# Smart_Bottle.net
KiCad netlist of a schematic drawn in Altium Designer
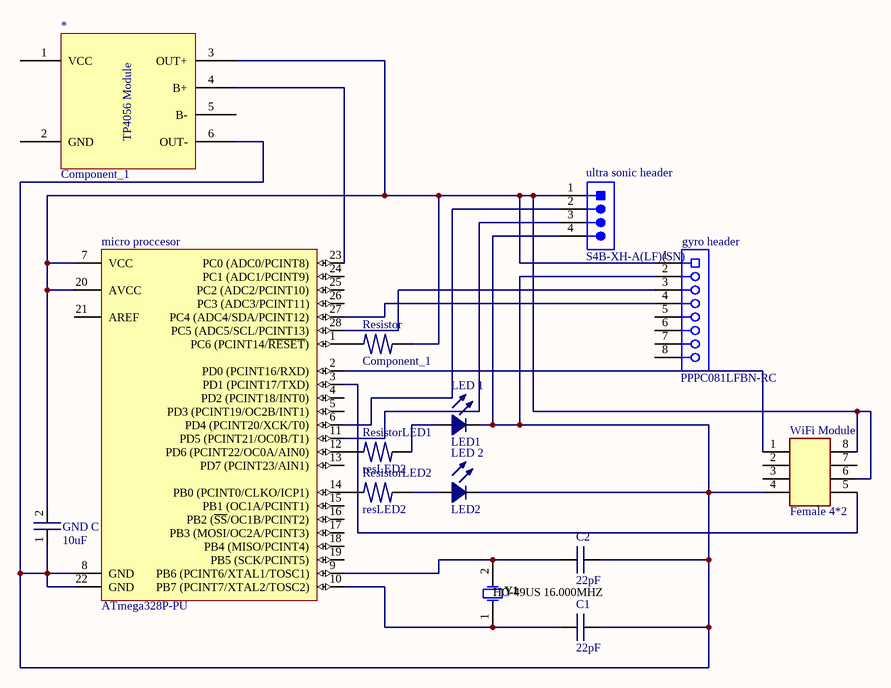
[diagram p0: Smart Bottle.SchDoc]

(export (version "E")
  (design (tool "Eeschema 10.0.6"))
  (components
    (comp (ref "*")
      (value "Component_1")
      (footprint "TP4056_6PINs")
      (libsource (lib "TP4056new") (part "Component_1"))
    )
    (comp (ref "C1")
      (value "22pF")
      (footprint "CAPACITOR 103")
      (libsource (lib "C capacitor") (part "Component_1"))
    )
    (comp (ref "C2")
      (value "22pF")
      (footprint "CAPACITOR 103")
      (libsource (lib "C capacitor") (part "Component_1"))
    )
    (comp (ref "GND C")
      (value "10uF")
      (footprint "CAPACITOR 103")
      (libsource (lib "") (part "Component_1_1"))
    )
    (comp (ref "gyro header")
      (value "PPPC081LFBN-RC")
      (footprint "SLIN-PPPC081LFBN-RC_V")
      (fields (field (name "MANUFACTURER") "Sullins"))
      (libsource (lib "University Of Moratuwa") (part "CN-1P-F-R8"))
    )
    (comp (ref "LED 1")
      (value "LED1")
      (footprint "LED_5mm_RED")
      (libsource (lib "LED1") (part "Component_1"))
    )
    (comp (ref "LED 2")
      (value "LED2")
      (footprint "LED_5mm_RED")
      (libsource (lib "LED1") (part "Component_1"))
    )
    (comp (ref "micro proccesor")
      (value "ATmega328P-PU")
      (footprint "28P3")
      (libsource (lib "Altium Content Vault") (part "MC-8B-ATM48-IL28"))
    )
    (comp (ref "Resistor")
      (value "Component_1")
      (footprint "RESSITOR_PTH_12.5mm")
      (libsource (lib "Resistor") (part "Component_1"))
    )
    (comp (ref "ResistorLED1")
      (value "resLED2")
      (footprint "RESSITOR_PTH_12.5mm")
      (libsource (lib "Resistor") (part "Component_1"))
    )
    (comp (ref "ResistorLED2")
      (value "resLED2")
      (footprint "RESSITOR_PTH_12.5mm")
      (libsource (lib "Resistor") (part "Component_1"))
    )
    (comp (ref "ultra sonic header")
      (value "S4B-XH-A(LF)(SN)")
      (footprint "JST-S4B-XH-A(LF)(SN)_V")
      (fields (field (name "MANUFACTURER") "JST"))
      (libsource (lib "University Of Moratuwa") (part "CN-1P-M-R4"))
    )
    (comp (ref "WiFi Module")
      (value "Female 4*2")
      (footprint "FEMALE_4X2")
      (libsource (lib "Female Header 4.2") (part "Component_1"))
    )
    (comp (ref "Y1")
      (value "HC-49US 16.000MHZ")
      (footprint "JPY-HC-49US")
      (description "Crystal, 16 MHz, +/- 30 ppm, 18 pF, -20 to 70 degC, 2-Pin THD")
      (fields (field (name "MANUFACTURER") "Jing peng yuan"))
      (libsource (lib "University Of Moratuwa") (part "XTAL-1-2-2"))
    )
  )
  (nets
    (net (code "1") (name "Net-(*-B+)") (class "Default")
      (node (ref "*") (pin "4") (pinfunction "B+_4") (pintype "passive"))
      (node (ref "micro proccesor") (pin "23") (pinfunction "PC0_(ADC0/PCINT8)_23") (pintype "bidirectional"))
    )
    (net (code "2") (name "Net-(*-OUT+)") (class "Default")
      (node (ref "*") (pin "3") (pinfunction "OUT+_3") (pintype "passive"))
      (node (ref "GND C") (pin "2") (pinfunction "2_2") (pintype "passive"))
      (node (ref "Resistor") (pin "2") (pinfunction "2_2") (pintype "passive"))
      (node (ref "WiFi Module") (pin "6") (pintype "passive"))
      (node (ref "WiFi Module") (pin "8") (pintype "passive"))
      (node (ref "gyro header") (pin "1") (pinfunction "1_1") (pintype "passive"))
      (node (ref "micro proccesor") (pin "20") (pinfunction "AVCC_20") (pintype "power_in"))
      (node (ref "micro proccesor") (pin "7") (pinfunction "VCC_7") (pintype "power_in"))
      (node (ref "ultra sonic header") (pin "1") (pinfunction "1_1") (pintype "passive"))
    )
    (net (code "3") (name "Net-(*-OUT-)") (class "Default")
      (node (ref "*") (pin "6") (pinfunction "OUT-_6") (pintype "passive"))
      (node (ref "C1") (pin "2") (pinfunction "2_2") (pintype "passive"))
      (node (ref "C2") (pin "2") (pinfunction "2_2") (pintype "passive"))
      (node (ref "GND C") (pin "1") (pinfunction "1_1") (pintype "passive"))
      (node (ref "LED 1") (pin "2") (pinfunction "2_2") (pintype "passive"))
      (node (ref "LED 2") (pin "2") (pinfunction "2_2") (pintype "passive"))
      (node (ref "WiFi Module") (pin "4") (pintype "passive"))
      (node (ref "gyro header") (pin "2") (pinfunction "2_2") (pintype "passive"))
      (node (ref "micro proccesor") (pin "22") (pinfunction "GND_22") (pintype "power_in"))
      (node (ref "micro proccesor") (pin "8") (pinfunction "GND_8") (pintype "power_in"))
      (node (ref "ultra sonic header") (pin "4") (pinfunction "4_4") (pintype "passive"))
    )
    (net (code "4") (name "Net-(LED 1-Pad1)") (class "Default")
      (node (ref "LED 1") (pin "1") (pinfunction "1_1") (pintype "passive"))
      (node (ref "ResistorLED1") (pin "2") (pinfunction "2_2") (pintype "passive"))
    )
    (net (code "5") (name "Net-(LED 2-Pad1)") (class "Default")
      (node (ref "LED 2") (pin "1") (pinfunction "1_1") (pintype "passive"))
      (node (ref "ResistorLED2") (pin "2") (pinfunction "2_2") (pintype "passive"))
    )
    (net (code "6") (name "Net-(micro proccesor-PB0_(PCINT0{slash}CLKO{slash}ICP1))") (class "Default")
      (node (ref "ResistorLED2") (pin "1") (pinfunction "1_1") (pintype "passive"))
      (node (ref "micro proccesor") (pin "14") (pinfunction "PB0_(PCINT0/CLKO/ICP1)_14") (pintype "bidirectional"))
    )
    (net (code "7") (name "Net-(micro proccesor-PB6_(PCINT6{slash}XTAL1{slash}TOSC1))") (class "Default")
      (node (ref "C2") (pin "1") (pinfunction "1_1") (pintype "passive"))
      (node (ref "Y1") (pin "2") (pinfunction "2_2") (pintype "passive"))
      (node (ref "micro proccesor") (pin "9") (pinfunction "PB6_(PCINT6/XTAL1/TOSC1)_9") (pintype "bidirectional"))
    )
    (net (code "8") (name "Net-(micro proccesor-PB7_(PCINT7{slash}XTAL2{slash}TOSC2))") (class "Default")
      (node (ref "C1") (pin "1") (pinfunction "1_1") (pintype "passive"))
      (node (ref "Y1") (pin "1") (pinfunction "1_1") (pintype "passive"))
      (node (ref "micro proccesor") (pin "10") (pinfunction "PB7_(PCINT7/XTAL2/TOSC2)_10") (pintype "bidirectional"))
    )
    (net (code "9") (name "Net-(micro proccesor-PC4_(ADC4{slash}SDA{slash}PCINT12))") (class "Default")
      (node (ref "gyro header") (pin "4") (pinfunction "4_4") (pintype "passive"))
      (node (ref "micro proccesor") (pin "27") (pinfunction "PC4_(ADC4/SDA/PCINT12)_27") (pintype "bidirectional"))
    )
    (net (code "10") (name "Net-(micro proccesor-PC5_(ADC5{slash}SCL{slash}PCINT13))") (class "Default")
      (node (ref "gyro header") (pin "3") (pinfunction "3_3") (pintype "passive"))
      (node (ref "micro proccesor") (pin "28") (pinfunction "PC5_(ADC5/SCL/PCINT13)_28") (pintype "bidirectional"))
    )
    (net (code "11") (name "Net-(micro proccesor-PC6_(PCINT14{slash}~{RESET}))") (class "Default")
      (node (ref "Resistor") (pin "1") (pinfunction "1_1") (pintype "passive"))
      (node (ref "micro proccesor") (pin "1") (pinfunction "PC6_(PCINT14/~{RESET})_1") (pintype "bidirectional"))
    )
    (net (code "12") (name "Net-(micro proccesor-PD0_(PCINT16{slash}RXD))") (class "Default")
      (node (ref "WiFi Module") (pin "1") (pintype "passive"))
      (node (ref "micro proccesor") (pin "2") (pinfunction "PD0_(PCINT16/RXD)_2") (pintype "bidirectional"))
    )
    (net (code "13") (name "Net-(micro proccesor-PD1_(PCINT17{slash}TXD))") (class "Default")
      (node (ref "WiFi Module") (pin "5") (pintype "passive"))
      (node (ref "micro proccesor") (pin "3") (pinfunction "PD1_(PCINT17/TXD)_3") (pintype "bidirectional"))
    )
    (net (code "14") (name "Net-(micro proccesor-PD4_(PCINT20{slash}XCK{slash}T0))") (class "Default")
      (node (ref "micro proccesor") (pin "6") (pinfunction "PD4_(PCINT20/XCK/T0)_6") (pintype "bidirectional"))
      (node (ref "ultra sonic header") (pin "2") (pinfunction "2_2") (pintype "passive"))
    )
    (net (code "15") (name "Net-(micro proccesor-PD5_(PCINT21{slash}OC0B{slash}T1))") (class "Default")
      (node (ref "micro proccesor") (pin "11") (pinfunction "PD5_(PCINT21/OC0B/T1)_11") (pintype "bidirectional"))
      (node (ref "ultra sonic header") (pin "3") (pinfunction "3_3") (pintype "passive"))
    )
    (net (code "16") (name "Net-(micro proccesor-PD6_(PCINT22{slash}OC0A{slash}AIN0))") (class "Default")
      (node (ref "ResistorLED1") (pin "1") (pinfunction "1_1") (pintype "passive"))
      (node (ref "micro proccesor") (pin "12") (pinfunction "PD6_(PCINT22/OC0A/AIN0)_12") (pintype "bidirectional"))
    )
    (net (code "17") (name "unconnected-(*-B--Pad5)") (class "Default")
      (node (ref "*") (pin "5") (pinfunction "B-_5") (pintype "passive"))
    )
    (net (code "18") (name "unconnected-(*-GND-Pad2)") (class "Default")
      (node (ref "*") (pin "2") (pinfunction "GND_2") (pintype "passive"))
    )
    (net (code "19") (name "unconnected-(*-VCC-Pad1)") (class "Default")
      (node (ref "*") (pin "1") (pinfunction "VCC_1") (pintype "passive"))
    )
    (net (code "20") (name "unconnected-(WiFi Module-Pad2)") (class "Default")
      (node (ref "WiFi Module") (pin "2") (pintype "passive"))
    )
    (net (code "21") (name "unconnected-(WiFi Module-Pad3)") (class "Default")
      (node (ref "WiFi Module") (pin "3") (pintype "passive"))
    )
    (net (code "22") (name "unconnected-(WiFi Module-Pad7)") (class "Default")
      (node (ref "WiFi Module") (pin "7") (pintype "passive"))
    )
    (net (code "23") (name "unconnected-(gyro header-Pad5)") (class "Default")
      (node (ref "gyro header") (pin "5") (pinfunction "5_5") (pintype "passive"))
    )
    (net (code "24") (name "unconnected-(gyro header-Pad6)") (class "Default")
      (node (ref "gyro header") (pin "6") (pinfunction "6_6") (pintype "passive"))
    )
    (net (code "25") (name "unconnected-(gyro header-Pad7)") (class "Default")
      (node (ref "gyro header") (pin "7") (pinfunction "7_7") (pintype "passive"))
    )
    (net (code "26") (name "unconnected-(gyro header-Pad8)") (class "Default")
      (node (ref "gyro header") (pin "8") (pinfunction "8_8") (pintype "passive"))
    )
    (net (code "27") (name "unconnected-(micro proccesor-AREF-Pad21)") (class "Default")
      (node (ref "micro proccesor") (pin "21") (pinfunction "AREF_21") (pintype "power_in"))
    )
    (net (code "28") (name "unconnected-(micro proccesor-PB1_(OC1A{slash}PCINT1)-Pad15)") (class "Default")
      (node (ref "micro proccesor") (pin "15") (pinfunction "PB1_(OC1A/PCINT1)_15") (pintype "bidirectional"))
    )
    (net (code "29") (name "unconnected-(micro proccesor-PB2_(~{SS}{slash}OC1B{slash}PCINT2)-Pad16)") (class "Default")
      (node (ref "micro proccesor") (pin "16") (pinfunction "PB2_(~{SS}/OC1B/PCINT2)_16") (pintype "bidirectional"))
    )
    (net (code "30") (name "unconnected-(micro proccesor-PB3_(MOSI{slash}OC2A{slash}PCINT3)-Pad17)") (class "Default")
      (node (ref "micro proccesor") (pin "17") (pinfunction "PB3_(MOSI/OC2A/PCINT3)_17") (pintype "bidirectional"))
    )
    (net (code "31") (name "unconnected-(micro proccesor-PB4_(MISO{slash}PCINT4)-Pad18)") (class "Default")
      (node (ref "micro proccesor") (pin "18") (pinfunction "PB4_(MISO/PCINT4)_18") (pintype "bidirectional"))
    )
    (net (code "32") (name "unconnected-(micro proccesor-PB5_(SCK{slash}PCINT5)-Pad19)") (class "Default")
      (node (ref "micro proccesor") (pin "19") (pinfunction "PB5_(SCK/PCINT5)_19") (pintype "bidirectional"))
    )
    (net (code "33") (name "unconnected-(micro proccesor-PC1_(ADC1{slash}PCINT9)-Pad24)") (class "Default")
      (node (ref "micro proccesor") (pin "24") (pinfunction "PC1_(ADC1/PCINT9)_24") (pintype "bidirectional"))
    )
    (net (code "34") (name "unconnected-(micro proccesor-PC2_(ADC2{slash}PCINT10)-Pad25)") (class "Default")
      (node (ref "micro proccesor") (pin "25") (pinfunction "PC2_(ADC2/PCINT10)_25") (pintype "bidirectional"))
    )
    (net (code "35") (name "unconnected-(micro proccesor-PC3_(ADC3{slash}PCINT11)-Pad26)") (class "Default")
      (node (ref "micro proccesor") (pin "26") (pinfunction "PC3_(ADC3/PCINT11)_26") (pintype "bidirectional"))
    )
    (net (code "36") (name "unconnected-(micro proccesor-PD2_(PCINT18{slash}INT0)-Pad4)") (class "Default")
      (node (ref "micro proccesor") (pin "4") (pinfunction "PD2_(PCINT18/INT0)_4") (pintype "bidirectional"))
    )
    (net (code "37") (name "unconnected-(micro proccesor-PD3_(PCINT19{slash}OC2B{slash}INT1)-Pad5)") (class "Default")
      (node (ref "micro proccesor") (pin "5") (pinfunction "PD3_(PCINT19/OC2B/INT1)_5") (pintype "bidirectional"))
    )
    (net (code "38") (name "unconnected-(micro proccesor-PD7_(PCINT23{slash}AIN1)-Pad13)") (class "Default")
      (node (ref "micro proccesor") (pin "13") (pinfunction "PD7_(PCINT23/AIN1)_13") (pintype "bidirectional"))
    )
  )
)
